# Bluetooth_and_OLED_Display.net
KiCad netlist of a schematic drawn in Altium Designer
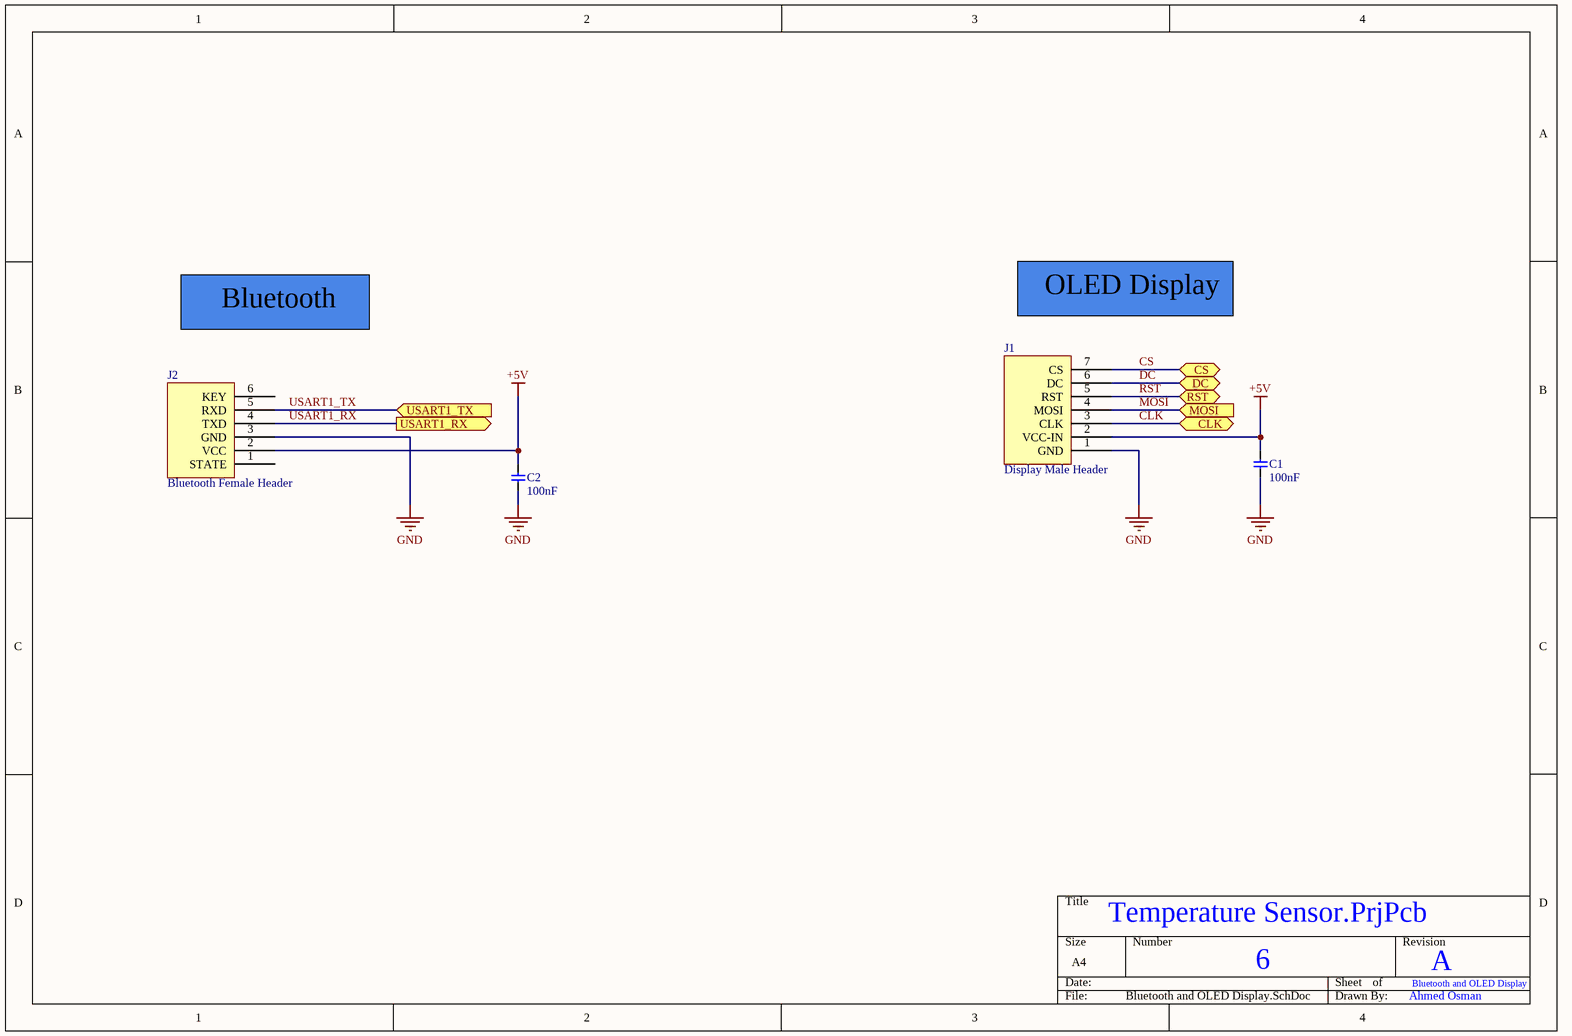
[diagram p0: Bluetooth and OLED Display.SchDoc]

(export (version "E")
  (design (tool "Eeschema 10.0.6"))
  (components
    (comp (ref "C1")
      (value "100nF")
      (footprint "CAP 0603")
      (description "0.1 µF ±10% 50V Ceramic Capacitor X7R 0603 (1608 Metric)")
      (fields (field (name "TOLERANCE") "10%") (field (name "VOLTAGE") "50V"))
      (libsource (lib "Temperature project symbols") (part "CAP  0603 100 nF 10% 50 V"))
    )
    (comp (ref "C2")
      (value "100nF")
      (footprint "CAP 0603")
      (description "0.1 µF ±10% 50V Ceramic Capacitor X7R 0603 (1608 Metric)")
      (fields (field (name "TOLERANCE") "10%") (field (name "VOLTAGE") "50V"))
      (libsource (lib "Temperature project symbols") (part "CAP  0603 100 nF 10% 50 V"))
    )
    (comp (ref "J1")
      (value "Display Male Header")
      (footprint "OLED Display")
      (libsource (lib "Temperature project symbols") (part "Display connector"))
    )
    (comp (ref "J2")
      (value "Bluetooth Female Header")
      (footprint "HC-05 Bluetooth")
      (libsource (lib "Temperature project symbols") (part "HC-05 Bluetooth Connector"))
    )
  )
  (nets
    (net (code "1") (name "+5V") (class "Default")
      (node (ref "C1") (pin "2") (pintype "passive"))
      (node (ref "C2") (pin "1") (pintype "passive"))
      (node (ref "J1") (pin "2") (pinfunction "VCC-IN_2") (pintype "passive"))
      (node (ref "J2") (pin "2") (pinfunction "VCC_2") (pintype "passive"))
    )
    (net (code "2") (name "/CLK") (class "Default")
      (node (ref "J1") (pin "3") (pinfunction "CLK_3") (pintype "passive"))
    )
    (net (code "3") (name "/CS") (class "Default")
      (node (ref "J1") (pin "7") (pinfunction "CS_7") (pintype "passive"))
    )
    (net (code "4") (name "/DC") (class "Default")
      (node (ref "J1") (pin "6") (pinfunction "DC_6") (pintype "passive"))
    )
    (net (code "5") (name "/MOSI") (class "Default")
      (node (ref "J1") (pin "4") (pinfunction "MOSI_4") (pintype "passive"))
    )
    (net (code "6") (name "/RST") (class "Default")
      (node (ref "J1") (pin "5") (pinfunction "RST_5") (pintype "passive"))
    )
    (net (code "7") (name "/USART1_RX") (class "Default")
      (node (ref "J2") (pin "4") (pinfunction "TXD_4") (pintype "passive"))
    )
    (net (code "8") (name "/USART1_TX") (class "Default")
      (node (ref "J2") (pin "5") (pinfunction "RXD_5") (pintype "passive"))
    )
    (net (code "9") (name "GND") (class "Default")
      (node (ref "C1") (pin "1") (pintype "passive"))
      (node (ref "C2") (pin "2") (pintype "passive"))
      (node (ref "J1") (pin "1") (pinfunction "GND_1") (pintype "passive"))
      (node (ref "J2") (pin "3") (pinfunction "GND_3") (pintype "passive"))
    )
    (net (code "10") (name "unconnected-(J2-KEY-Pad6)") (class "Default")
      (node (ref "J2") (pin "6") (pinfunction "KEY_6") (pintype "passive"))
    )
    (net (code "11") (name "unconnected-(J2-STATE-Pad1)") (class "Default")
      (node (ref "J2") (pin "1") (pinfunction "STATE_1") (pintype "passive"))
    )
  )
)
